# VCLPF.net
KiCad netlist of a schematic drawn in Altium Designer
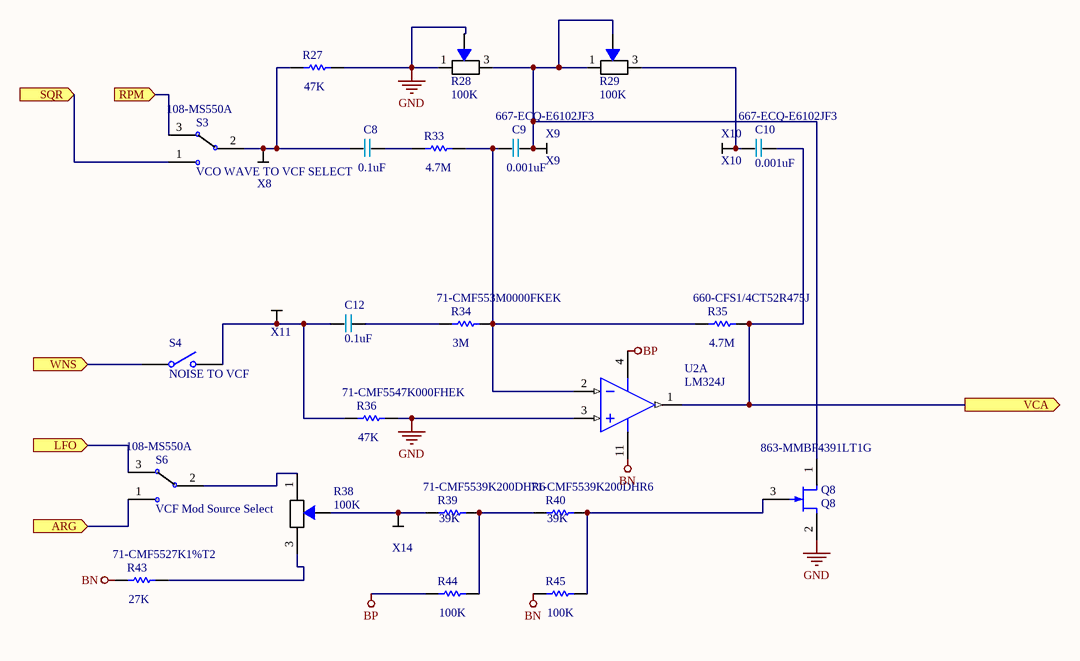
[diagram p0: VCLPF.SchDoc]

(export (version "E")
  (design (tool "Eeschema 10.0.6"))
  (components
    (comp (ref "C8")
      (value "0.1uF")
      (footprint "Cap Film 5")
      (libsource (lib "MyLibrary") (part "Cap Film 5"))
    )
    (comp (ref "C9")
      (value "0.001uF")
      (footprint "Cap Film 5")
      (fields
        (field (name "SUPPLIER PART NUMBER 1") "667-ECQ-E6102JF3")
        (field (name "MANUFACTURER") "Panasonic")
        (field (name "MANUFACTURER PART NUMBER") "ECQ-E4103KF")
        (field (name "TOLERANCE") "5 %")
      )
      (libsource (lib "MyLibrary") (part "Cap Film 5"))
    )
    (comp (ref "C10")
      (value "0.001uF")
      (footprint "Cap Film 5")
      (fields
        (field (name "SUPPLIER PART NUMBER 1") "667-ECQ-E6102JF3")
        (field (name "MANUFACTURER") "Panasonic")
        (field (name "MANUFACTURER PART NUMBER") "ECQ-E6102JF3")
        (field (name "TOLERANCE") "5 %")
      )
      (libsource (lib "MyLibrary") (part "Cap Film 5"))
    )
    (comp (ref "C12")
      (value "0.1uF")
      (footprint "Cap Film 5")
      (libsource (lib "MyLibrary") (part "Cap Film 5"))
    )
    (comp (ref "Q8")
      (value "Q8")
      (footprint "ONSC-SOT-23-3-318-08_V")
      (description "JFET Switching Transistor, N-Channel, 3-Pin SOT-23, Tape and Reel")
      (fields
        (field (name "MANUFACTURER") "On Semiconductor")
        (field (name "PARTNUMBER") "MMBF4391LT1")
        (field (name "SUPPLIER PART NUMBER 2") "863-MMBF4391LT1G")
      )
      (libsource (lib "ON Semi JFETs") (part "MMBF4391LT1"))
    )
    (comp (ref "R27")
      (value "47K")
      (footprint "AXIAL-0.3")
      (description "Resistor")
      (fields
        (field (name "MANUFACTURER PART NUMBER") "CMF5547K000FHEK")
        (field (name "PUBLISHER") "Altium Limited")
      )
      (libsource (lib "Miscellaneous Devices") (part "Res1"))
    )
    (comp (ref "R28")
      (value "100K")
      (footprint "Potentiometer")
      (description "My Own")
      (fields
        (field (name "MANUFACTURER") "Alpha (Taiwan)")
        (field (name "MANUFACTURER PART NUMBER") "RV09AF-40-20K-B100K")
      )
      (libsource (lib "MyLibrary") (part "Potentiometer"))
    )
    (comp (ref "R29")
      (value "100K")
      (footprint "Potentiometer")
      (description "My Own")
      (fields
        (field (name "MANUFACTURER") "Alpha (Taiwan)")
        (field (name "MANUFACTURER PART NUMBER") "RV09AF-40-20K-B100K")
      )
      (libsource (lib "MyLibrary") (part "Potentiometer"))
    )
    (comp (ref "R33")
      (value "4.7M")
      (footprint "AXIAL-0.3")
      (description "Resistor")
      (fields (field (name "PUBLISHER") "Altium Limited"))
      (libsource (lib "Miscellaneous Devices") (part "Res1"))
    )
    (comp (ref "R34")
      (value "3M")
      (footprint "AXIAL-0.3")
      (description "Resistor")
      (fields
        (field (name "SUPPLIER PART NUMBER 1") "71-CMF553M0000FKEK")
        (field (name "MANUFACTURER") "Vishay / Dale")
        (field (name "MANUFACTURER PART NUMBER") "CMF553M0000FKEK")
        (field (name "PUBLISHER") "Altium Limited")
      )
      (libsource (lib "Miscellaneous Devices") (part "Res1"))
    )
    (comp (ref "R35")
      (value "4.7M")
      (footprint "AXIAL-0.3")
      (description "Resistor")
      (fields
        (field (name "SUPPLIER PART NUMBER 1") "660-CFS1/4CT52R475J")
        (field (name "MANUFACTURER") "KOA Speer")
        (field (name "MANUFACTURER PART NUMBER") "CFS1/4CT52R475J")
        (field (name "PUBLISHER") "Altium Limited")
      )
      (libsource (lib "Miscellaneous Devices") (part "Res1"))
    )
    (comp (ref "R36")
      (value "47K")
      (footprint "AXIAL-0.3")
      (description "Resistor")
      (fields
        (field (name "SUPPLIER PART NUMBER 1") "71-CMF5547K000FHEK")
        (field (name "MANUFACTURER") "Vishay / Dale")
        (field (name "MANUFACTURER PART NUMBER") "CMF5547K000FHEK")
        (field (name "PUBLISHER") "Altium Limited")
      )
      (libsource (lib "Miscellaneous Devices") (part "Res1"))
    )
    (comp (ref "R38")
      (value "100K")
      (footprint "Potentiometer")
      (description "My Own")
      (fields
        (field (name "MANUFACTURER") "Alpha (Taiwan)")
        (field (name "MANUFACTURER PART NUMBER") "RV09AF-40-20K-B100K")
      )
      (libsource (lib "") (part "Potentiometer_1"))
    )
    (comp (ref "R39")
      (value "39K")
      (footprint "AXIAL-0.3")
      (description "Resistor")
      (fields
        (field (name "SUPPLIER PART NUMBER 1") "71-CMF5539K200DHR6")
        (field (name "MANUFACTURER") "Vishay / Dale")
        (field (name "MANUFACTURER PART NUMBER") "CMF5539K200DHR6")
        (field (name "PUBLISHER") "Altium Limited")
      )
      (libsource (lib "Miscellaneous Devices") (part "Res1"))
    )
    (comp (ref "R40")
      (value "39K")
      (footprint "AXIAL-0.3")
      (description "Resistor")
      (fields
        (field (name "SUPPLIER PART NUMBER 1") "71-CMF5539K200DHR6")
        (field (name "MANUFACTURER") "Vishay / Dale")
        (field (name "MANUFACTURER PART NUMBER") "CMF5539K200DHR6")
        (field (name "PUBLISHER") "Altium Limited")
      )
      (libsource (lib "Miscellaneous Devices") (part "Res1"))
    )
    (comp (ref "R43")
      (value "27K")
      (footprint "AXIAL-0.3")
      (description "Resistor")
      (fields
        (field (name "SUPPLIER PART NUMBER 1") "71-CMF5527K1%T2")
        (field (name "MANUFACTURER") "Vishay / Dale")
        (field (name "MANUFACTURER PART NUMBER") "CMF5527K000FHBF")
        (field (name "PUBLISHER") "Altium Limited")
      )
      (libsource (lib "Miscellaneous Devices") (part "Res1"))
    )
    (comp (ref "R44")
      (value "100K")
      (footprint "AXIAL-0.3")
      (description "Resistor")
      (fields
        (field (name "MANUFACTURER") "Vishay / Dale")
        (field (name "MANUFACTURER PART NUMBER") "CMF55100K00FHEK")
        (field (name "PUBLISHER") "Altium Limited")
      )
      (libsource (lib "Miscellaneous Devices") (part "Res1"))
    )
    (comp (ref "R45")
      (value "100K")
      (footprint "AXIAL-0.3")
      (description "Resistor")
      (fields
        (field (name "MANUFACTURER") "Vishay / Dale")
        (field (name "MANUFACTURER PART NUMBER") "CMF55100K00FHEK")
        (field (name "PUBLISHER") "Altium Limited")
      )
      (libsource (lib "Miscellaneous Devices") (part "Res1"))
    )
    (comp (ref "S3")
      (value "VCO WAVE TO VCF SELECT")
      (footprint "SPDT Switch")
      (description "SPDT Switch")
      (fields
        (field (name "SUPPLIER PART NUMBER 1") "108-MS550A")
        (field (name "MANUFACTURER") "Mountain Switch")
        (field (name "MANUFACTURER PART NUMBER") "108-MS550A")
      )
      (libsource (lib "MyLibrary") (part "SPDT Switch"))
    )
    (comp (ref "S4")
      (value "NOISE TO VCF")
      (footprint "SPST-2")
      (description "Single-Pole, Single-Throw Switch")
      (fields (field (name "PUBLISHER") "Altium Limited"))
      (libsource (lib "Miscellaneous Devices") (part "SW-SPST"))
    )
    (comp (ref "S6")
      (value "VCF Mod Source Select")
      (footprint "SPDT Switch")
      (description "SPDT Switch")
      (fields
        (field (name "SUPPLIER PART NUMBER 1") "108-MS550A")
        (field (name "MANUFACTURER") "Mountain Switch")
        (field (name "MANUFACTURER PART NUMBER") "108-MS550A")
      )
      (libsource (lib "MyLibrary") (part "SPDT Switch"))
    )
    (comp (ref "U2")
      (value "LM324J")
      (footprint "J14A")
      (description "Low Power Quad Operational Amplifier, 14-pin CerDIP")
      (fields (field (name "MANUFACTURER") "National Semiconductor"))
      (libsource (lib "National Semiconductor Amplifier") (part "LM324J"))
    )
    (comp (ref "X8") (value "Pad") (footprint "Pad") (libsource (lib "MyLibrary") (part "Pad")))
    (comp (ref "X9") (value "X9") (footprint "Pad") (libsource (lib "MyLibrary") (part "Pad")))
    (comp (ref "X10") (value "X10") (footprint "Pad") (libsource (lib "MyLibrary") (part "Pad")))
    (comp (ref "X11") (value "X11") (footprint "Pad") (libsource (lib "MyLibrary") (part "Pad")))
    (comp (ref "X14") (value "X14") (footprint "Pad") (libsource (lib "MyLibrary") (part "Pad")))
  )
  (nets
    (net (code "1") (name "/ARG") (class "Default")
      (node (ref "S6") (pin "1") (pinfunction "1_1") (pintype "passive"))
    )
    (net (code "2") (name "/LFO") (class "Default")
      (node (ref "S6") (pin "3") (pinfunction "3_3") (pintype "passive"))
    )
    (net (code "3") (name "/RPM") (class "Default")
      (node (ref "S3") (pin "3") (pinfunction "3_3") (pintype "passive"))
    )
    (net (code "4") (name "/SQR") (class "Default")
      (node (ref "S3") (pin "1") (pinfunction "1_1") (pintype "passive"))
    )
    (net (code "5") (name "/VCA") (class "Default")
      (node (ref "C10") (pin "2") (pinfunction "2_2") (pintype "passive"))
      (node (ref "R35") (pin "2") (pinfunction "2_2") (pintype "passive"))
      (node (ref "U2") (pin "1") (pinfunction "OUT1_1") (pintype "output"))
    )
    (net (code "6") (name "/WNS") (class "Default")
      (node (ref "S4") (pin "1") (pinfunction "COMMON_1") (pintype "passive"))
    )
    (net (code "7") (name "BN") (class "Default")
      (node (ref "R43") (pin "1") (pinfunction "1_1") (pintype "passive"))
      (node (ref "R45") (pin "1") (pinfunction "1_1") (pintype "passive"))
      (node (ref "U2") (pin "11") (pinfunction "GND_11") (pintype "power_in"))
    )
    (net (code "8") (name "BP") (class "Default")
      (node (ref "R44") (pin "1") (pinfunction "1_1") (pintype "passive"))
      (node (ref "U2") (pin "4") (pinfunction "V+_4") (pintype "power_in"))
    )
    (net (code "9") (name "GND") (class "Default")
      (node (ref "Q8") (pin "2") (pinfunction "S_2") (pintype "passive"))
      (node (ref "R27") (pin "2") (pinfunction "2_2") (pintype "passive"))
      (node (ref "R28") (pin "1") (pinfunction "1_1") (pintype "passive"))
      (node (ref "R28") (pin "2") (pinfunction "2_2") (pintype "passive"))
      (node (ref "R36") (pin "2") (pinfunction "2_2") (pintype "passive"))
      (node (ref "U2") (pin "3") (pinfunction "IN1+_3") (pintype "input"))
    )
    (net (code "10") (name "Net-(C8-Pad1)") (class "Default")
      (node (ref "C8") (pin "1") (pinfunction "1_1") (pintype "passive"))
      (node (ref "R27") (pin "1") (pinfunction "1_1") (pintype "passive"))
      (node (ref "S3") (pin "2") (pinfunction "2_2") (pintype "passive"))
      (node (ref "X8") (pin "1") (pinfunction "1_1") (pintype "passive"))
    )
    (net (code "11") (name "Net-(C8-Pad2)") (class "Default")
      (node (ref "C8") (pin "2") (pinfunction "2_2") (pintype "passive"))
      (node (ref "R33") (pin "1") (pinfunction "1_1") (pintype "passive"))
    )
    (net (code "12") (name "Net-(C10-Pad1)") (class "Default")
      (node (ref "C10") (pin "1") (pinfunction "1_1") (pintype "passive"))
      (node (ref "R29") (pin "3") (pinfunction "3_3") (pintype "passive"))
      (node (ref "X10") (pin "1") (pinfunction "1_1") (pintype "passive"))
    )
    (net (code "13") (name "Net-(C12-Pad2)") (class "Default")
      (node (ref "C12") (pin "2") (pinfunction "2_2") (pintype "passive"))
      (node (ref "R34") (pin "1") (pinfunction "1_1") (pintype "passive"))
    )
    (net (code "14") (name "Net-(Q8-D)") (class "Default")
      (node (ref "C9") (pin "2") (pinfunction "2_2") (pintype "passive"))
      (node (ref "Q8") (pin "1") (pinfunction "D_1") (pintype "passive"))
      (node (ref "R28") (pin "3") (pinfunction "3_3") (pintype "passive"))
      (node (ref "R29") (pin "1") (pinfunction "1_1") (pintype "passive"))
      (node (ref "R29") (pin "2") (pinfunction "2_2") (pintype "passive"))
      (node (ref "X9") (pin "1") (pinfunction "1_1") (pintype "passive"))
    )
    (net (code "15") (name "Net-(Q8-G)") (class "Default")
      (node (ref "Q8") (pin "3") (pinfunction "G_3") (pintype "passive"))
      (node (ref "R40") (pin "2") (pinfunction "2_2") (pintype "passive"))
      (node (ref "R45") (pin "2") (pinfunction "2_2") (pintype "passive"))
    )
    (net (code "16") (name "Net-(R38-Pad1)") (class "Default")
      (node (ref "R38") (pin "1") (pinfunction "1_1") (pintype "passive"))
      (node (ref "S6") (pin "2") (pinfunction "2_2") (pintype "passive"))
    )
    (net (code "17") (name "Net-(R38-Pad2)") (class "Default")
      (node (ref "R38") (pin "2") (pinfunction "2_2") (pintype "passive"))
      (node (ref "R39") (pin "1") (pinfunction "1_1") (pintype "passive"))
      (node (ref "X14") (pin "1") (pinfunction "1_1") (pintype "passive"))
    )
    (net (code "18") (name "Net-(R38-Pad3)") (class "Default")
      (node (ref "R38") (pin "3") (pinfunction "3_3") (pintype "passive"))
      (node (ref "R43") (pin "2") (pinfunction "2_2") (pintype "passive"))
    )
    (net (code "19") (name "Net-(R39-Pad2)") (class "Default")
      (node (ref "R39") (pin "2") (pinfunction "2_2") (pintype "passive"))
      (node (ref "R40") (pin "1") (pinfunction "1_1") (pintype "passive"))
      (node (ref "R44") (pin "2") (pinfunction "2_2") (pintype "passive"))
    )
    (net (code "20") (name "Net-(S4-NO)") (class "Default")
      (node (ref "C12") (pin "1") (pinfunction "1_1") (pintype "passive"))
      (node (ref "R36") (pin "1") (pinfunction "1_1") (pintype "passive"))
      (node (ref "S4") (pin "2") (pinfunction "NO_2") (pintype "passive"))
      (node (ref "X11") (pin "1") (pinfunction "1_1") (pintype "passive"))
    )
    (net (code "21") (name "Net-(U2A-IN1-)") (class "Default")
      (node (ref "C9") (pin "1") (pinfunction "1_1") (pintype "passive"))
      (node (ref "R33") (pin "2") (pinfunction "2_2") (pintype "passive"))
      (node (ref "R34") (pin "2") (pinfunction "2_2") (pintype "passive"))
      (node (ref "R35") (pin "1") (pinfunction "1_1") (pintype "passive"))
      (node (ref "U2") (pin "2") (pinfunction "IN1-_2") (pintype "input"))
    )
  )
)
